# 5_ZynTra-Zynq-PL.net
KiCad netlist of a schematic drawn in Altium Designer
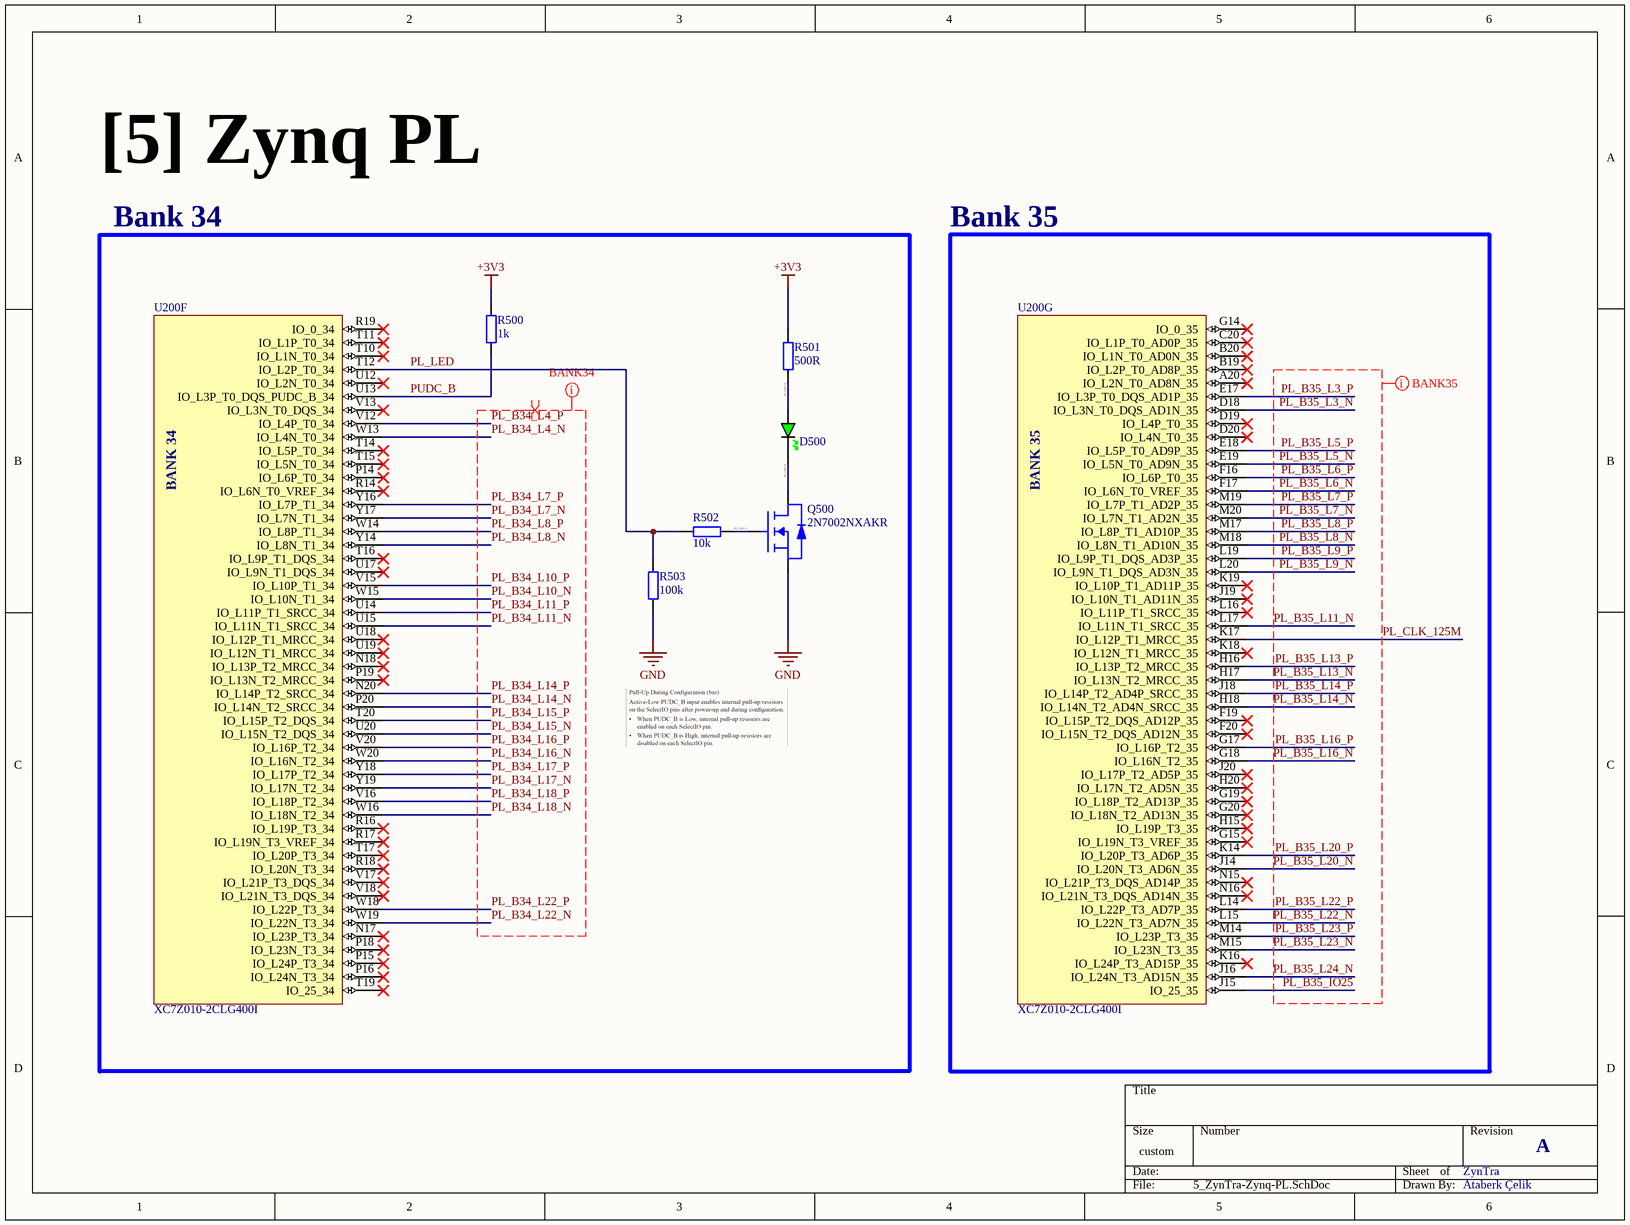
[diagram p0: 5_ZynTra-Zynq-PL.SchDoc]

(export (version "E")
  (design (tool "Eeschema 10.0.6"))
  (components
    (comp (ref "D500")
      (value "GREEN")
      (footprint "LED_0603_GREEN")
      (description "LED 0603 GREEN SMD")
      (libsource (lib "Schematic-Lib-PhilsLab") (part "LED_0603_GREEN"))
    )
    (comp (ref "Q500")
      (value "2N7002NXAKR")
      (footprint "SSM3J338R,LF-SOT23-F")
      (description "MOSFET N-Channel Vds=60V Id=300mA with ESD Protection")
      (fields (field (name "MANUFACTURER") "Nexperia"))
      (libsource (lib "Schematic-Lib-PhilsLab") (part "2N7002NXAKR"))
    )
    (comp (ref "R500")
      (value "1k")
      (footprint "RES_0402")
      (description "Resistor SMD 0402")
      (libsource (lib "Schematic-Lib-PhilsLab") (part "RES_0402"))
    )
    (comp (ref "R501")
      (value "500R")
      (footprint "RES_0402")
      (description "Resistor SMD 0402")
      (libsource (lib "Schematic-Lib-PhilsLab") (part "RES_0402"))
    )
    (comp (ref "R502")
      (value "10k")
      (footprint "RES_0402")
      (description "Resistor SMD 0402")
      (libsource (lib "Schematic-Lib-PhilsLab") (part "RES_0402"))
    )
    (comp (ref "R503")
      (value "100k")
      (footprint "RES_0402")
      (description "Resistor SMD 0402")
      (libsource (lib "Schematic-Lib-PhilsLab") (part "RES_0402"))
    )
    (comp (ref "U200")
      (value "XC7Z010-2CLG400I")
      (footprint "CLG400, 0.8mm, 17x17")
      (fields (field (name "MANUFACTURER") "AMD / Xilinx"))
      (libsource (lib "") (part "XC7Z010-2CLG400I_1"))
    )
  )
  (nets
    (net (code "1") (name "+3V3") (class "Default")
      (node (ref "R500") (pin "1") (pinfunction "1_1") (pintype "passive"))
      (node (ref "R501") (pin "1") (pinfunction "1_1") (pintype "passive"))
    )
    (net (code "2") (name "/PL_B34_L4_N") (class "Default")
      (node (ref "U200") (pin "W13") (pinfunction "IO_L4N_T0_34_W13") (pintype "bidirectional"))
    )
    (net (code "3") (name "/PL_B34_L4_P") (class "Default")
      (node (ref "U200") (pin "V12") (pinfunction "IO_L4P_T0_34_V12") (pintype "bidirectional"))
    )
    (net (code "4") (name "/PL_B34_L7_N") (class "Default")
      (node (ref "U200") (pin "Y17") (pinfunction "IO_L7N_T1_34_Y17") (pintype "bidirectional"))
    )
    (net (code "5") (name "/PL_B34_L7_P") (class "Default")
      (node (ref "U200") (pin "Y16") (pinfunction "IO_L7P_T1_34_Y16") (pintype "bidirectional"))
    )
    (net (code "6") (name "/PL_B34_L8_N") (class "Default")
      (node (ref "U200") (pin "Y14") (pinfunction "IO_L8N_T1_34_Y14") (pintype "bidirectional"))
    )
    (net (code "7") (name "/PL_B34_L8_P") (class "Default")
      (node (ref "U200") (pin "W14") (pinfunction "IO_L8P_T1_34_W14") (pintype "bidirectional"))
    )
    (net (code "8") (name "/PL_B34_L10_N") (class "Default")
      (node (ref "U200") (pin "W15") (pinfunction "IO_L10N_T1_34_W15") (pintype "bidirectional"))
    )
    (net (code "9") (name "/PL_B34_L10_P") (class "Default")
      (node (ref "U200") (pin "V15") (pinfunction "IO_L10P_T1_34_V15") (pintype "bidirectional"))
    )
    (net (code "10") (name "/PL_B34_L11_N") (class "Default")
      (node (ref "U200") (pin "U15") (pinfunction "IO_L11N_T1_SRCC_34_U15") (pintype "bidirectional"))
    )
    (net (code "11") (name "/PL_B34_L11_P") (class "Default")
      (node (ref "U200") (pin "U14") (pinfunction "IO_L11P_T1_SRCC_34_U14") (pintype "bidirectional"))
    )
    (net (code "12") (name "/PL_B34_L14_N") (class "Default")
      (node (ref "U200") (pin "P20") (pinfunction "IO_L14N_T2_SRCC_34_P20") (pintype "bidirectional"))
    )
    (net (code "13") (name "/PL_B34_L14_P") (class "Default")
      (node (ref "U200") (pin "N20") (pinfunction "IO_L14P_T2_SRCC_34_N20") (pintype "bidirectional"))
    )
    (net (code "14") (name "/PL_B34_L15_N") (class "Default")
      (node (ref "U200") (pin "U20") (pinfunction "IO_L15N_T2_DQS_34_U20") (pintype "bidirectional"))
    )
    (net (code "15") (name "/PL_B34_L15_P") (class "Default")
      (node (ref "U200") (pin "T20") (pinfunction "IO_L15P_T2_DQS_34_T20") (pintype "bidirectional"))
    )
    (net (code "16") (name "/PL_B34_L16_N") (class "Default")
      (node (ref "U200") (pin "W20") (pinfunction "IO_L16N_T2_34_W20") (pintype "bidirectional"))
    )
    (net (code "17") (name "/PL_B34_L16_P") (class "Default")
      (node (ref "U200") (pin "V20") (pinfunction "IO_L16P_T2_34_V20") (pintype "bidirectional"))
    )
    (net (code "18") (name "/PL_B34_L17_N") (class "Default")
      (node (ref "U200") (pin "Y19") (pinfunction "IO_L17N_T2_34_Y19") (pintype "bidirectional"))
    )
    (net (code "19") (name "/PL_B34_L17_P") (class "Default")
      (node (ref "U200") (pin "Y18") (pinfunction "IO_L17P_T2_34_Y18") (pintype "bidirectional"))
    )
    (net (code "20") (name "/PL_B34_L18_N") (class "Default")
      (node (ref "U200") (pin "W16") (pinfunction "IO_L18N_T2_34_W16") (pintype "bidirectional"))
    )
    (net (code "21") (name "/PL_B34_L18_P") (class "Default")
      (node (ref "U200") (pin "V16") (pinfunction "IO_L18P_T2_34_V16") (pintype "bidirectional"))
    )
    (net (code "22") (name "/PL_B34_L22_N") (class "Default")
      (node (ref "U200") (pin "W19") (pinfunction "IO_L22N_T3_34_W19") (pintype "bidirectional"))
    )
    (net (code "23") (name "/PL_B34_L22_P") (class "Default")
      (node (ref "U200") (pin "W18") (pinfunction "IO_L22P_T3_34_W18") (pintype "bidirectional"))
    )
    (net (code "24") (name "/PL_B35_IO25") (class "Default")
      (node (ref "U200") (pin "J15") (pinfunction "IO_25_35_J15") (pintype "bidirectional"))
    )
    (net (code "25") (name "/PL_B35_L3_N") (class "Default")
      (node (ref "U200") (pin "D18") (pinfunction "IO_L3N_T0_DQS_AD1N_35_D18") (pintype "bidirectional"))
    )
    (net (code "26") (name "/PL_B35_L3_P") (class "Default")
      (node (ref "U200") (pin "E17") (pinfunction "IO_L3P_T0_DQS_AD1P_35_E17") (pintype "bidirectional"))
    )
    (net (code "27") (name "/PL_B35_L5_N") (class "Default")
      (node (ref "U200") (pin "E19") (pinfunction "IO_L5N_T0_AD9N_35_E19") (pintype "bidirectional"))
    )
    (net (code "28") (name "/PL_B35_L5_P") (class "Default")
      (node (ref "U200") (pin "E18") (pinfunction "IO_L5P_T0_AD9P_35_E18") (pintype "bidirectional"))
    )
    (net (code "29") (name "/PL_B35_L6_N") (class "Default")
      (node (ref "U200") (pin "F17") (pinfunction "IO_L6N_T0_VREF_35_F17") (pintype "bidirectional"))
    )
    (net (code "30") (name "/PL_B35_L6_P") (class "Default")
      (node (ref "U200") (pin "F16") (pinfunction "IO_L6P_T0_35_F16") (pintype "bidirectional"))
    )
    (net (code "31") (name "/PL_B35_L7_N") (class "Default")
      (node (ref "U200") (pin "M20") (pinfunction "IO_L7N_T1_AD2N_35_M20") (pintype "bidirectional"))
    )
    (net (code "32") (name "/PL_B35_L7_P") (class "Default")
      (node (ref "U200") (pin "M19") (pinfunction "IO_L7P_T1_AD2P_35_M19") (pintype "bidirectional"))
    )
    (net (code "33") (name "/PL_B35_L8_N") (class "Default")
      (node (ref "U200") (pin "M18") (pinfunction "IO_L8N_T1_AD10N_35_M18") (pintype "bidirectional"))
    )
    (net (code "34") (name "/PL_B35_L8_P") (class "Default")
      (node (ref "U200") (pin "M17") (pinfunction "IO_L8P_T1_AD10P_35_M17") (pintype "bidirectional"))
    )
    (net (code "35") (name "/PL_B35_L9_N") (class "Default")
      (node (ref "U200") (pin "L20") (pinfunction "IO_L9N_T1_DQS_AD3N_35_L20") (pintype "bidirectional"))
    )
    (net (code "36") (name "/PL_B35_L9_P") (class "Default")
      (node (ref "U200") (pin "L19") (pinfunction "IO_L9P_T1_DQS_AD3P_35_L19") (pintype "bidirectional"))
    )
    (net (code "37") (name "/PL_B35_L11_N") (class "Default")
      (node (ref "U200") (pin "L17") (pinfunction "IO_L11N_T1_SRCC_35_L17") (pintype "bidirectional"))
    )
    (net (code "38") (name "/PL_B35_L13_N") (class "Default")
      (node (ref "U200") (pin "H17") (pinfunction "IO_L13N_T2_MRCC_35_H17") (pintype "bidirectional"))
    )
    (net (code "39") (name "/PL_B35_L13_P") (class "Default")
      (node (ref "U200") (pin "H16") (pinfunction "IO_L13P_T2_MRCC_35_H16") (pintype "bidirectional"))
    )
    (net (code "40") (name "/PL_B35_L14_N") (class "Default")
      (node (ref "U200") (pin "H18") (pinfunction "IO_L14N_T2_AD4N_SRCC_35_H18") (pintype "bidirectional"))
    )
    (net (code "41") (name "/PL_B35_L14_P") (class "Default")
      (node (ref "U200") (pin "J18") (pinfunction "IO_L14P_T2_AD4P_SRCC_35_J18") (pintype "bidirectional"))
    )
    (net (code "42") (name "/PL_B35_L16_N") (class "Default")
      (node (ref "U200") (pin "G18") (pinfunction "IO_L16N_T2_35_G18") (pintype "bidirectional"))
    )
    (net (code "43") (name "/PL_B35_L16_P") (class "Default")
      (node (ref "U200") (pin "G17") (pinfunction "IO_L16P_T2_35_G17") (pintype "bidirectional"))
    )
    (net (code "44") (name "/PL_B35_L20_N") (class "Default")
      (node (ref "U200") (pin "J14") (pinfunction "IO_L20N_T3_AD6N_35_J14") (pintype "bidirectional"))
    )
    (net (code "45") (name "/PL_B35_L20_P") (class "Default")
      (node (ref "U200") (pin "K14") (pinfunction "IO_L20P_T3_AD6P_35_K14") (pintype "bidirectional"))
    )
    (net (code "46") (name "/PL_B35_L22_N") (class "Default")
      (node (ref "U200") (pin "L15") (pinfunction "IO_L22N_T3_AD7N_35_L15") (pintype "bidirectional"))
    )
    (net (code "47") (name "/PL_B35_L22_P") (class "Default")
      (node (ref "U200") (pin "L14") (pinfunction "IO_L22P_T3_AD7P_35_L14") (pintype "bidirectional"))
    )
    (net (code "48") (name "/PL_B35_L23_N") (class "Default")
      (node (ref "U200") (pin "M15") (pinfunction "IO_L23N_T3_35_M15") (pintype "bidirectional"))
    )
    (net (code "49") (name "/PL_B35_L23_P") (class "Default")
      (node (ref "U200") (pin "M14") (pinfunction "IO_L23P_T3_35_M14") (pintype "bidirectional"))
    )
    (net (code "50") (name "/PL_B35_L24_N") (class "Default")
      (node (ref "U200") (pin "J16") (pinfunction "IO_L24N_T3_AD15N_35_J16") (pintype "bidirectional"))
    )
    (net (code "51") (name "/PL_CLK_125M") (class "Default")
      (node (ref "U200") (pin "K17") (pinfunction "IO_L12P_T1_MRCC_35_K17") (pintype "bidirectional"))
    )
    (net (code "52") (name "/PL_LED") (class "Default")
      (node (ref "R502") (pin "1") (pinfunction "1_1") (pintype "passive"))
      (node (ref "R503") (pin "1") (pinfunction "1_1") (pintype "passive"))
      (node (ref "U200") (pin "T12") (pinfunction "IO_L2P_T0_34_T12") (pintype "bidirectional"))
    )
    (net (code "53") (name "/PL_LED_A") (class "Default")
      (node (ref "D500") (pin "A") (pinfunction "A_A") (pintype "passive"))
      (node (ref "R501") (pin "2") (pinfunction "2_2") (pintype "passive"))
    )
    (net (code "54") (name "/PL_LED_G") (class "Default")
      (node (ref "Q500") (pin "G") (pinfunction "G_G") (pintype "passive"))
      (node (ref "R502") (pin "2") (pinfunction "2_2") (pintype "passive"))
    )
    (net (code "55") (name "/PL_LED_K") (class "Default")
      (node (ref "D500") (pin "K") (pinfunction "K_K") (pintype "passive"))
      (node (ref "Q500") (pin "D") (pinfunction "D_D") (pintype "passive"))
    )
    (net (code "56") (name "/PUDC_B") (class "Default")
      (node (ref "R500") (pin "2") (pinfunction "2_2") (pintype "passive"))
      (node (ref "U200") (pin "U13") (pinfunction "IO_L3P_T0_DQS_PUDC_B_34_U13") (pintype "bidirectional"))
    )
    (net (code "57") (name "GND") (class "Default")
      (node (ref "Q500") (pin "S") (pinfunction "S_S") (pintype "passive"))
      (node (ref "R503") (pin "2") (pinfunction "2_2") (pintype "passive"))
    )
    (net (code "58") (name "unconnected-(U200F-IO_0_34-PadR19)") (class "Default")
      (node (ref "U200") (pin "R19") (pinfunction "IO_0_34_R19") (pintype "bidirectional+no_connect"))
    )
    (net (code "59") (name "unconnected-(U200F-IO_25_34-PadT19)") (class "Default")
      (node (ref "U200") (pin "T19") (pinfunction "IO_25_34_T19") (pintype "bidirectional+no_connect"))
    )
    (net (code "60") (name "unconnected-(U200F-IO_L1N_T0_34-PadT10)") (class "Default")
      (node (ref "U200") (pin "T10") (pinfunction "IO_L1N_T0_34_T10") (pintype "bidirectional+no_connect"))
    )
    (net (code "61") (name "unconnected-(U200F-IO_L1P_T0_34-PadT11)") (class "Default")
      (node (ref "U200") (pin "T11") (pinfunction "IO_L1P_T0_34_T11") (pintype "bidirectional+no_connect"))
    )
    (net (code "62") (name "unconnected-(U200F-IO_L2N_T0_34-PadU12)") (class "Default")
      (node (ref "U200") (pin "U12") (pinfunction "IO_L2N_T0_34_U12") (pintype "bidirectional+no_connect"))
    )
    (net (code "63") (name "unconnected-(U200F-IO_L3N_T0_DQS_34-PadV13)") (class "Default")
      (node (ref "U200") (pin "V13") (pinfunction "IO_L3N_T0_DQS_34_V13") (pintype "bidirectional+no_connect"))
    )
    (net (code "64") (name "unconnected-(U200F-IO_L5N_T0_34-PadT15)") (class "Default")
      (node (ref "U200") (pin "T15") (pinfunction "IO_L5N_T0_34_T15") (pintype "bidirectional+no_connect"))
    )
    (net (code "65") (name "unconnected-(U200F-IO_L5P_T0_34-PadT14)") (class "Default")
      (node (ref "U200") (pin "T14") (pinfunction "IO_L5P_T0_34_T14") (pintype "bidirectional+no_connect"))
    )
    (net (code "66") (name "unconnected-(U200F-IO_L6N_T0_VREF_34-PadR14)") (class "Default")
      (node (ref "U200") (pin "R14") (pinfunction "IO_L6N_T0_VREF_34_R14") (pintype "bidirectional+no_connect"))
    )
    (net (code "67") (name "unconnected-(U200F-IO_L6P_T0_34-PadP14)") (class "Default")
      (node (ref "U200") (pin "P14") (pinfunction "IO_L6P_T0_34_P14") (pintype "bidirectional+no_connect"))
    )
    (net (code "68") (name "unconnected-(U200F-IO_L9N_T1_DQS_34-PadU17)") (class "Default")
      (node (ref "U200") (pin "U17") (pinfunction "IO_L9N_T1_DQS_34_U17") (pintype "bidirectional+no_connect"))
    )
    (net (code "69") (name "unconnected-(U200F-IO_L9P_T1_DQS_34-PadT16)") (class "Default")
      (node (ref "U200") (pin "T16") (pinfunction "IO_L9P_T1_DQS_34_T16") (pintype "bidirectional+no_connect"))
    )
    (net (code "70") (name "unconnected-(U200F-IO_L12N_T1_MRCC_34-PadU19)") (class "Default")
      (node (ref "U200") (pin "U19") (pinfunction "IO_L12N_T1_MRCC_34_U19") (pintype "bidirectional+no_connect"))
    )
    (net (code "71") (name "unconnected-(U200F-IO_L12P_T1_MRCC_34-PadU18)") (class "Default")
      (node (ref "U200") (pin "U18") (pinfunction "IO_L12P_T1_MRCC_34_U18") (pintype "bidirectional+no_connect"))
    )
    (net (code "72") (name "unconnected-(U200F-IO_L13N_T2_MRCC_34-PadP19)") (class "Default")
      (node (ref "U200") (pin "P19") (pinfunction "IO_L13N_T2_MRCC_34_P19") (pintype "bidirectional+no_connect"))
    )
    (net (code "73") (name "unconnected-(U200F-IO_L13P_T2_MRCC_34-PadN18)") (class "Default")
      (node (ref "U200") (pin "N18") (pinfunction "IO_L13P_T2_MRCC_34_N18") (pintype "bidirectional+no_connect"))
    )
    (net (code "74") (name "unconnected-(U200F-IO_L19N_T3_VREF_34-PadR17)") (class "Default")
      (node (ref "U200") (pin "R17") (pinfunction "IO_L19N_T3_VREF_34_R17") (pintype "bidirectional+no_connect"))
    )
    (net (code "75") (name "unconnected-(U200F-IO_L19P_T3_34-PadR16)") (class "Default")
      (node (ref "U200") (pin "R16") (pinfunction "IO_L19P_T3_34_R16") (pintype "bidirectional+no_connect"))
    )
    (net (code "76") (name "unconnected-(U200F-IO_L20N_T3_34-PadR18)") (class "Default")
      (node (ref "U200") (pin "R18") (pinfunction "IO_L20N_T3_34_R18") (pintype "bidirectional+no_connect"))
    )
    (net (code "77") (name "unconnected-(U200F-IO_L20P_T3_34-PadT17)") (class "Default")
      (node (ref "U200") (pin "T17") (pinfunction "IO_L20P_T3_34_T17") (pintype "bidirectional+no_connect"))
    )
    (net (code "78") (name "unconnected-(U200F-IO_L21N_T3_DQS_34-PadV18)") (class "Default")
      (node (ref "U200") (pin "V18") (pinfunction "IO_L21N_T3_DQS_34_V18") (pintype "bidirectional+no_connect"))
    )
    (net (code "79") (name "unconnected-(U200F-IO_L21P_T3_DQS_34-PadV17)") (class "Default")
      (node (ref "U200") (pin "V17") (pinfunction "IO_L21P_T3_DQS_34_V17") (pintype "bidirectional+no_connect"))
    )
    (net (code "80") (name "unconnected-(U200F-IO_L23N_T3_34-PadP18)") (class "Default")
      (node (ref "U200") (pin "P18") (pinfunction "IO_L23N_T3_34_P18") (pintype "bidirectional+no_connect"))
    )
    (net (code "81") (name "unconnected-(U200F-IO_L23P_T3_34-PadN17)") (class "Default")
      (node (ref "U200") (pin "N17") (pinfunction "IO_L23P_T3_34_N17") (pintype "bidirectional+no_connect"))
    )
    (net (code "82") (name "unconnected-(U200F-IO_L24N_T3_34-PadP16)") (class "Default")
      (node (ref "U200") (pin "P16") (pinfunction "IO_L24N_T3_34_P16") (pintype "bidirectional+no_connect"))
    )
    (net (code "83") (name "unconnected-(U200F-IO_L24P_T3_34-PadP15)") (class "Default")
      (node (ref "U200") (pin "P15") (pinfunction "IO_L24P_T3_34_P15") (pintype "bidirectional+no_connect"))
    )
    (net (code "84") (name "unconnected-(U200G-IO_0_35-PadG14)") (class "Default")
      (node (ref "U200") (pin "G14") (pinfunction "IO_0_35_G14") (pintype "bidirectional+no_connect"))
    )
    (net (code "85") (name "unconnected-(U200G-IO_L1N_T0_AD0N_35-PadB20)") (class "Default")
      (node (ref "U200") (pin "B20") (pinfunction "IO_L1N_T0_AD0N_35_B20") (pintype "bidirectional+no_connect"))
    )
    (net (code "86") (name "unconnected-(U200G-IO_L1P_T0_AD0P_35-PadC20)") (class "Default")
      (node (ref "U200") (pin "C20") (pinfunction "IO_L1P_T0_AD0P_35_C20") (pintype "bidirectional+no_connect"))
    )
    (net (code "87") (name "unconnected-(U200G-IO_L2N_T0_AD8N_35-PadA20)") (class "Default")
      (node (ref "U200") (pin "A20") (pinfunction "IO_L2N_T0_AD8N_35_A20") (pintype "bidirectional+no_connect"))
    )
    (net (code "88") (name "unconnected-(U200G-IO_L2P_T0_AD8P_35-PadB19)") (class "Default")
      (node (ref "U200") (pin "B19") (pinfunction "IO_L2P_T0_AD8P_35_B19") (pintype "bidirectional+no_connect"))
    )
    (net (code "89") (name "unconnected-(U200G-IO_L4N_T0_35-PadD20)") (class "Default")
      (node (ref "U200") (pin "D20") (pinfunction "IO_L4N_T0_35_D20") (pintype "bidirectional+no_connect"))
    )
    (net (code "90") (name "unconnected-(U200G-IO_L4P_T0_35-PadD19)") (class "Default")
      (node (ref "U200") (pin "D19") (pinfunction "IO_L4P_T0_35_D19") (pintype "bidirectional+no_connect"))
    )
    (net (code "91") (name "unconnected-(U200G-IO_L10N_T1_AD11N_35-PadJ19)") (class "Default")
      (node (ref "U200") (pin "J19") (pinfunction "IO_L10N_T1_AD11N_35_J19") (pintype "bidirectional+no_connect"))
    )
    (net (code "92") (name "unconnected-(U200G-IO_L10P_T1_AD11P_35-PadK19)") (class "Default")
      (node (ref "U200") (pin "K19") (pinfunction "IO_L10P_T1_AD11P_35_K19") (pintype "bidirectional+no_connect"))
    )
    (net (code "93") (name "unconnected-(U200G-IO_L11P_T1_SRCC_35-PadL16)") (class "Default")
      (node (ref "U200") (pin "L16") (pinfunction "IO_L11P_T1_SRCC_35_L16") (pintype "bidirectional+no_connect"))
    )
    (net (code "94") (name "unconnected-(U200G-IO_L12N_T1_MRCC_35-PadK18)") (class "Default")
      (node (ref "U200") (pin "K18") (pinfunction "IO_L12N_T1_MRCC_35_K18") (pintype "bidirectional+no_connect"))
    )
    (net (code "95") (name "unconnected-(U200G-IO_L15N_T2_DQS_AD12N_35-PadF20)") (class "Default")
      (node (ref "U200") (pin "F20") (pinfunction "IO_L15N_T2_DQS_AD12N_35_F20") (pintype "bidirectional+no_connect"))
    )
    (net (code "96") (name "unconnected-(U200G-IO_L15P_T2_DQS_AD12P_35-PadF19)") (class "Default")
      (node (ref "U200") (pin "F19") (pinfunction "IO_L15P_T2_DQS_AD12P_35_F19") (pintype "bidirectional+no_connect"))
    )
    (net (code "97") (name "unconnected-(U200G-IO_L17N_T2_AD5N_35-PadH20)") (class "Default")
      (node (ref "U200") (pin "H20") (pinfunction "IO_L17N_T2_AD5N_35_H20") (pintype "bidirectional+no_connect"))
    )
    (net (code "98") (name "unconnected-(U200G-IO_L17P_T2_AD5P_35-PadJ20)") (class "Default")
      (node (ref "U200") (pin "J20") (pinfunction "IO_L17P_T2_AD5P_35_J20") (pintype "bidirectional+no_connect"))
    )
    (net (code "99") (name "unconnected-(U200G-IO_L18N_T2_AD13N_35-PadG20)") (class "Default")
      (node (ref "U200") (pin "G20") (pinfunction "IO_L18N_T2_AD13N_35_G20") (pintype "bidirectional+no_connect"))
    )
    (net (code "100") (name "unconnected-(U200G-IO_L18P_T2_AD13P_35-PadG19)") (class "Default")
      (node (ref "U200") (pin "G19") (pinfunction "IO_L18P_T2_AD13P_35_G19") (pintype "bidirectional+no_connect"))
    )
    (net (code "101") (name "unconnected-(U200G-IO_L19N_T3_VREF_35-PadG15)") (class "Default")
      (node (ref "U200") (pin "G15") (pinfunction "IO_L19N_T3_VREF_35_G15") (pintype "bidirectional+no_connect"))
    )
    (net (code "102") (name "unconnected-(U200G-IO_L19P_T3_35-PadH15)") (class "Default")
      (node (ref "U200") (pin "H15") (pinfunction "IO_L19P_T3_35_H15") (pintype "bidirectional+no_connect"))
    )
    (net (code "103") (name "unconnected-(U200G-IO_L21N_T3_DQS_AD14N_35-PadN16)") (class "Default")
      (node (ref "U200") (pin "N16") (pinfunction "IO_L21N_T3_DQS_AD14N_35_N16") (pintype "bidirectional+no_connect"))
    )
    (net (code "104") (name "unconnected-(U200G-IO_L21P_T3_DQS_AD14P_35-PadN15)") (class "Default")
      (node (ref "U200") (pin "N15") (pinfunction "IO_L21P_T3_DQS_AD14P_35_N15") (pintype "bidirectional+no_connect"))
    )
    (net (code "105") (name "unconnected-(U200G-IO_L24P_T3_AD15P_35-PadK16)") (class "Default")
      (node (ref "U200") (pin "K16") (pinfunction "IO_L24P_T3_AD15P_35_K16") (pintype "bidirectional+no_connect"))
    )
  )
)
